# Digital_Greippi.net
KiCad netlist of a schematic drawn in EAGLE
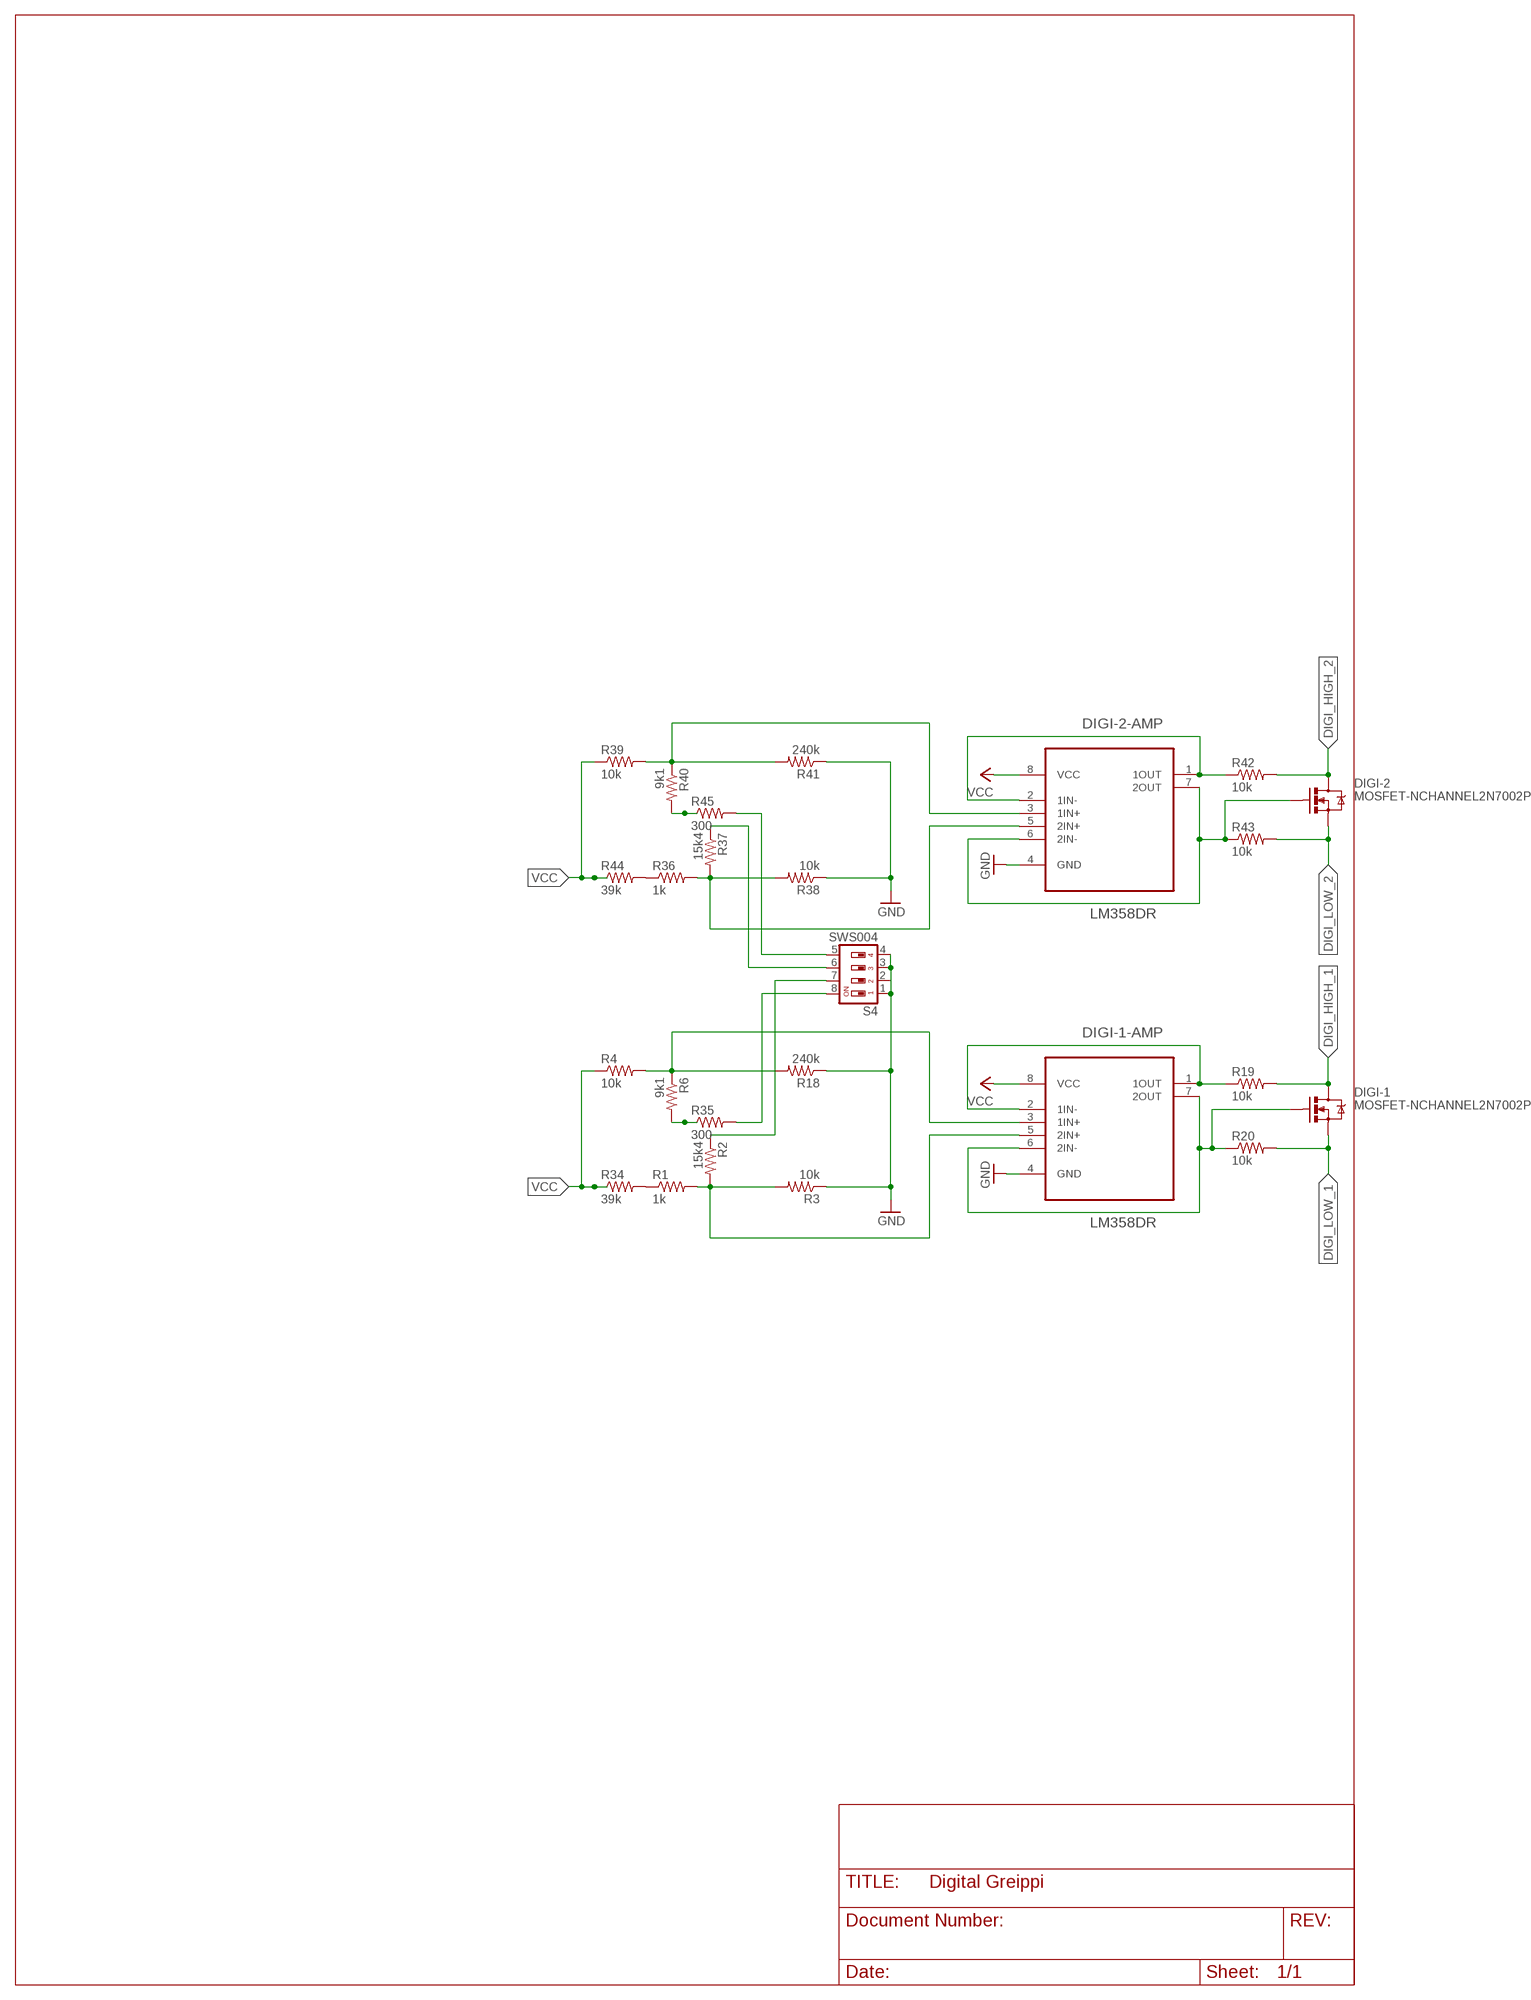
[diagram p0: schematic, sheet 1]

(export (version "E")
  (design (tool "Eeschema 10.0.6"))
  (components
    (comp (ref "DIGI-1")
      (value "MOSFET-NCHANNEL2N7002PW")
      (footprint "eagle-import:SOT323")
      (libsource (lib "eagle-import") (part "MOSFET-NCHANNEL2N7002PW"))
    )
    (comp (ref "DIGI-1-AMP")
      (value "LM358DR")
      (footprint "eagle-import:SOIC127P600X175-8N")
      (libsource (lib "eagle-import") (part "LM358DR"))
    )
    (comp (ref "DIGI-2")
      (value "MOSFET-NCHANNEL2N7002PW")
      (footprint "eagle-import:SOT323")
      (libsource (lib "eagle-import") (part "MOSFET-NCHANNEL2N7002PW"))
    )
    (comp (ref "DIGI-2-AMP")
      (value "LM358DR")
      (footprint "eagle-import:SOIC127P600X175-8N")
      (libsource (lib "eagle-import") (part "LM358DR"))
    )
    (comp (ref "R1")
      (value "1k")
      (footprint "eagle-import:R0805")
      (libsource (lib "eagle-import") (part "R-US_R0805"))
    )
    (comp (ref "R2")
      (value "15k4")
      (footprint "eagle-import:R0805")
      (libsource (lib "eagle-import") (part "R-US_R0805"))
    )
    (comp (ref "R3")
      (value "10k")
      (footprint "eagle-import:R0805")
      (libsource (lib "eagle-import") (part "R-US_R0805"))
    )
    (comp (ref "R4")
      (value "10k")
      (footprint "eagle-import:R0805")
      (libsource (lib "eagle-import") (part "R-US_R0805"))
    )
    (comp (ref "R6")
      (value "9k1")
      (footprint "eagle-import:R0805")
      (libsource (lib "eagle-import") (part "R-US_R0805"))
    )
    (comp (ref "R18")
      (value "240k")
      (footprint "eagle-import:R0805")
      (libsource (lib "eagle-import") (part "R-US_R0805"))
    )
    (comp (ref "R19")
      (value "10k")
      (footprint "eagle-import:R0805")
      (libsource (lib "eagle-import") (part "R-US_R0805"))
    )
    (comp (ref "R20")
      (value "10k")
      (footprint "eagle-import:R0805")
      (libsource (lib "eagle-import") (part "R-US_R0805"))
    )
    (comp (ref "R34")
      (value "39k")
      (footprint "eagle-import:R0805")
      (libsource (lib "eagle-import") (part "R-US_R0805"))
    )
    (comp (ref "R35")
      (value "300")
      (footprint "eagle-import:R0805")
      (libsource (lib "eagle-import") (part "R-US_R0805"))
    )
    (comp (ref "R36")
      (value "1k")
      (footprint "eagle-import:R0805")
      (libsource (lib "eagle-import") (part "R-US_R0805"))
    )
    (comp (ref "R37")
      (value "15k4")
      (footprint "eagle-import:R0805")
      (libsource (lib "eagle-import") (part "R-US_R0805"))
    )
    (comp (ref "R38")
      (value "10k")
      (footprint "eagle-import:R0805")
      (libsource (lib "eagle-import") (part "R-US_R0805"))
    )
    (comp (ref "R39")
      (value "10k")
      (footprint "eagle-import:R0805")
      (libsource (lib "eagle-import") (part "R-US_R0805"))
    )
    (comp (ref "R40")
      (value "9k1")
      (footprint "eagle-import:R0805")
      (libsource (lib "eagle-import") (part "R-US_R0805"))
    )
    (comp (ref "R41")
      (value "240k")
      (footprint "eagle-import:R0805")
      (libsource (lib "eagle-import") (part "R-US_R0805"))
    )
    (comp (ref "R42")
      (value "10k")
      (footprint "eagle-import:R0805")
      (libsource (lib "eagle-import") (part "R-US_R0805"))
    )
    (comp (ref "R43")
      (value "10k")
      (footprint "eagle-import:R0805")
      (libsource (lib "eagle-import") (part "R-US_R0805"))
    )
    (comp (ref "R44")
      (value "39k")
      (footprint "eagle-import:R0805")
      (libsource (lib "eagle-import") (part "R-US_R0805"))
    )
    (comp (ref "R45")
      (value "300")
      (footprint "eagle-import:R0805")
      (libsource (lib "eagle-import") (part "R-US_R0805"))
    )
    (comp (ref "S4")
      (value "SWS004")
      (footprint "eagle-import:SMS-004")
      (libsource (lib "eagle-import") (part "SWS004"))
    )
  )
  (nets
    (net (code "1") (name "DIGI_HIGH_1") (class "Default")
      (node (ref "DIGI-1") (pin "3") (pinfunction "D_3") (pintype "passive"))
      (node (ref "R19") (pin "2") (pinfunction "2_2") (pintype "passive"))
    )
    (net (code "2") (name "DIGI_HIGH_2") (class "Default")
      (node (ref "DIGI-2") (pin "3") (pinfunction "D_3") (pintype "passive"))
      (node (ref "R42") (pin "2") (pinfunction "2_2") (pintype "passive"))
    )
    (net (code "3") (name "DIGI_LOW_1") (class "Default")
      (node (ref "DIGI-1") (pin "2") (pinfunction "S_2") (pintype "passive"))
      (node (ref "R20") (pin "2") (pinfunction "2_2") (pintype "passive"))
    )
    (net (code "4") (name "DIGI_LOW_2") (class "Default")
      (node (ref "DIGI-2") (pin "2") (pinfunction "S_2") (pintype "passive"))
      (node (ref "R43") (pin "2") (pinfunction "2_2") (pintype "passive"))
    )
    (net (code "5") (name "GND") (class "Default")
      (node (ref "DIGI-1-AMP") (pin "4") (pinfunction "GND_4") (pintype "passive"))
      (node (ref "DIGI-2-AMP") (pin "4") (pinfunction "GND_4") (pintype "passive"))
      (node (ref "R18") (pin "1") (pinfunction "1_1") (pintype "passive"))
      (node (ref "R3") (pin "1") (pinfunction "1_1") (pintype "passive"))
      (node (ref "R38") (pin "1") (pinfunction "1_1") (pintype "passive"))
      (node (ref "R41") (pin "1") (pinfunction "1_1") (pintype "passive"))
      (node (ref "S4") (pin "1") (pinfunction "1_1") (pintype "passive"))
      (node (ref "S4") (pin "2") (pinfunction "2_2") (pintype "passive"))
      (node (ref "S4") (pin "3") (pinfunction "3_3") (pintype "passive"))
      (node (ref "S4") (pin "4") (pinfunction "4_4") (pintype "passive"))
    )
    (net (code "6") (name "Net-(DIGI-1-AMP-1IN+)") (class "Default")
      (node (ref "DIGI-1-AMP") (pin "3") (pinfunction "1IN+_3") (pintype "input"))
      (node (ref "R18") (pin "2") (pinfunction "2_2") (pintype "passive"))
      (node (ref "R4") (pin "2") (pinfunction "2_2") (pintype "passive"))
      (node (ref "R6") (pin "1") (pinfunction "1_1") (pintype "passive"))
    )
    (net (code "7") (name "Net-(DIGI-1-AMP-1IN-)") (class "Default")
      (node (ref "DIGI-1-AMP") (pin "1") (pinfunction "1OUT_1") (pintype "output"))
      (node (ref "DIGI-1-AMP") (pin "2") (pinfunction "1IN-_2") (pintype "input"))
      (node (ref "R19") (pin "1") (pinfunction "1_1") (pintype "passive"))
    )
    (net (code "8") (name "Net-(DIGI-1-AMP-2IN+)") (class "Default")
      (node (ref "DIGI-1-AMP") (pin "5") (pinfunction "2IN+_5") (pintype "input"))
      (node (ref "R1") (pin "2") (pinfunction "2_2") (pintype "passive"))
      (node (ref "R2") (pin "2") (pinfunction "2_2") (pintype "passive"))
      (node (ref "R3") (pin "2") (pinfunction "2_2") (pintype "passive"))
    )
    (net (code "9") (name "Net-(DIGI-1-AMP-2IN-)") (class "Default")
      (node (ref "DIGI-1") (pin "1") (pinfunction "G_1") (pintype "passive"))
      (node (ref "DIGI-1-AMP") (pin "6") (pinfunction "2IN-_6") (pintype "input"))
      (node (ref "DIGI-1-AMP") (pin "7") (pinfunction "2OUT_7") (pintype "output"))
      (node (ref "R20") (pin "1") (pinfunction "1_1") (pintype "passive"))
    )
    (net (code "10") (name "Net-(DIGI-2-AMP-1IN+)") (class "Default")
      (node (ref "DIGI-2-AMP") (pin "3") (pinfunction "1IN+_3") (pintype "input"))
      (node (ref "R39") (pin "2") (pinfunction "2_2") (pintype "passive"))
      (node (ref "R40") (pin "1") (pinfunction "1_1") (pintype "passive"))
      (node (ref "R41") (pin "2") (pinfunction "2_2") (pintype "passive"))
    )
    (net (code "11") (name "Net-(DIGI-2-AMP-1IN-)") (class "Default")
      (node (ref "DIGI-2-AMP") (pin "1") (pinfunction "1OUT_1") (pintype "output"))
      (node (ref "DIGI-2-AMP") (pin "2") (pinfunction "1IN-_2") (pintype "input"))
      (node (ref "R42") (pin "1") (pinfunction "1_1") (pintype "passive"))
    )
    (net (code "12") (name "Net-(DIGI-2-AMP-2IN+)") (class "Default")
      (node (ref "DIGI-2-AMP") (pin "5") (pinfunction "2IN+_5") (pintype "input"))
      (node (ref "R36") (pin "2") (pinfunction "2_2") (pintype "passive"))
      (node (ref "R37") (pin "2") (pinfunction "2_2") (pintype "passive"))
      (node (ref "R38") (pin "2") (pinfunction "2_2") (pintype "passive"))
    )
    (net (code "13") (name "Net-(DIGI-2-AMP-2IN-)") (class "Default")
      (node (ref "DIGI-2") (pin "1") (pinfunction "G_1") (pintype "passive"))
      (node (ref "DIGI-2-AMP") (pin "6") (pinfunction "2IN-_6") (pintype "input"))
      (node (ref "DIGI-2-AMP") (pin "7") (pinfunction "2OUT_7") (pintype "output"))
      (node (ref "R43") (pin "1") (pinfunction "1_1") (pintype "passive"))
    )
    (net (code "14") (name "Net-(R1-Pad1)") (class "Default")
      (node (ref "R1") (pin "1") (pinfunction "1_1") (pintype "passive"))
      (node (ref "R34") (pin "2") (pinfunction "2_2") (pintype "passive"))
    )
    (net (code "15") (name "Net-(R2-Pad1)") (class "Default")
      (node (ref "R2") (pin "1") (pinfunction "1_1") (pintype "passive"))
      (node (ref "S4") (pin "7") (pinfunction "7_7") (pintype "passive"))
    )
    (net (code "16") (name "Net-(R35-Pad1)") (class "Default")
      (node (ref "R35") (pin "1") (pinfunction "1_1") (pintype "passive"))
      (node (ref "R6") (pin "2") (pinfunction "2_2") (pintype "passive"))
    )
    (net (code "17") (name "Net-(R35-Pad2)") (class "Default")
      (node (ref "R35") (pin "2") (pinfunction "2_2") (pintype "passive"))
      (node (ref "S4") (pin "8") (pinfunction "8_8") (pintype "passive"))
    )
    (net (code "18") (name "Net-(R36-Pad1)") (class "Default")
      (node (ref "R36") (pin "1") (pinfunction "1_1") (pintype "passive"))
      (node (ref "R44") (pin "2") (pinfunction "2_2") (pintype "passive"))
    )
    (net (code "19") (name "Net-(R37-Pad1)") (class "Default")
      (node (ref "R37") (pin "1") (pinfunction "1_1") (pintype "passive"))
      (node (ref "S4") (pin "6") (pinfunction "6_6") (pintype "passive"))
    )
    (net (code "20") (name "Net-(R40-Pad2)") (class "Default")
      (node (ref "R40") (pin "2") (pinfunction "2_2") (pintype "passive"))
      (node (ref "R45") (pin "1") (pinfunction "1_1") (pintype "passive"))
    )
    (net (code "21") (name "Net-(R45-Pad2)") (class "Default")
      (node (ref "R45") (pin "2") (pinfunction "2_2") (pintype "passive"))
      (node (ref "S4") (pin "5") (pinfunction "5_5") (pintype "passive"))
    )
    (net (code "22") (name "VCC") (class "Default")
      (node (ref "DIGI-1-AMP") (pin "8") (pinfunction "VCC_8") (pintype "power_in"))
      (node (ref "DIGI-2-AMP") (pin "8") (pinfunction "VCC_8") (pintype "power_in"))
      (node (ref "R34") (pin "1") (pinfunction "1_1") (pintype "passive"))
      (node (ref "R39") (pin "1") (pinfunction "1_1") (pintype "passive"))
      (node (ref "R4") (pin "1") (pinfunction "1_1") (pintype "passive"))
      (node (ref "R44") (pin "1") (pinfunction "1_1") (pintype "passive"))
    )
  )
)
